# HDMI.net
KiCad netlist of a schematic drawn in Altium Designer
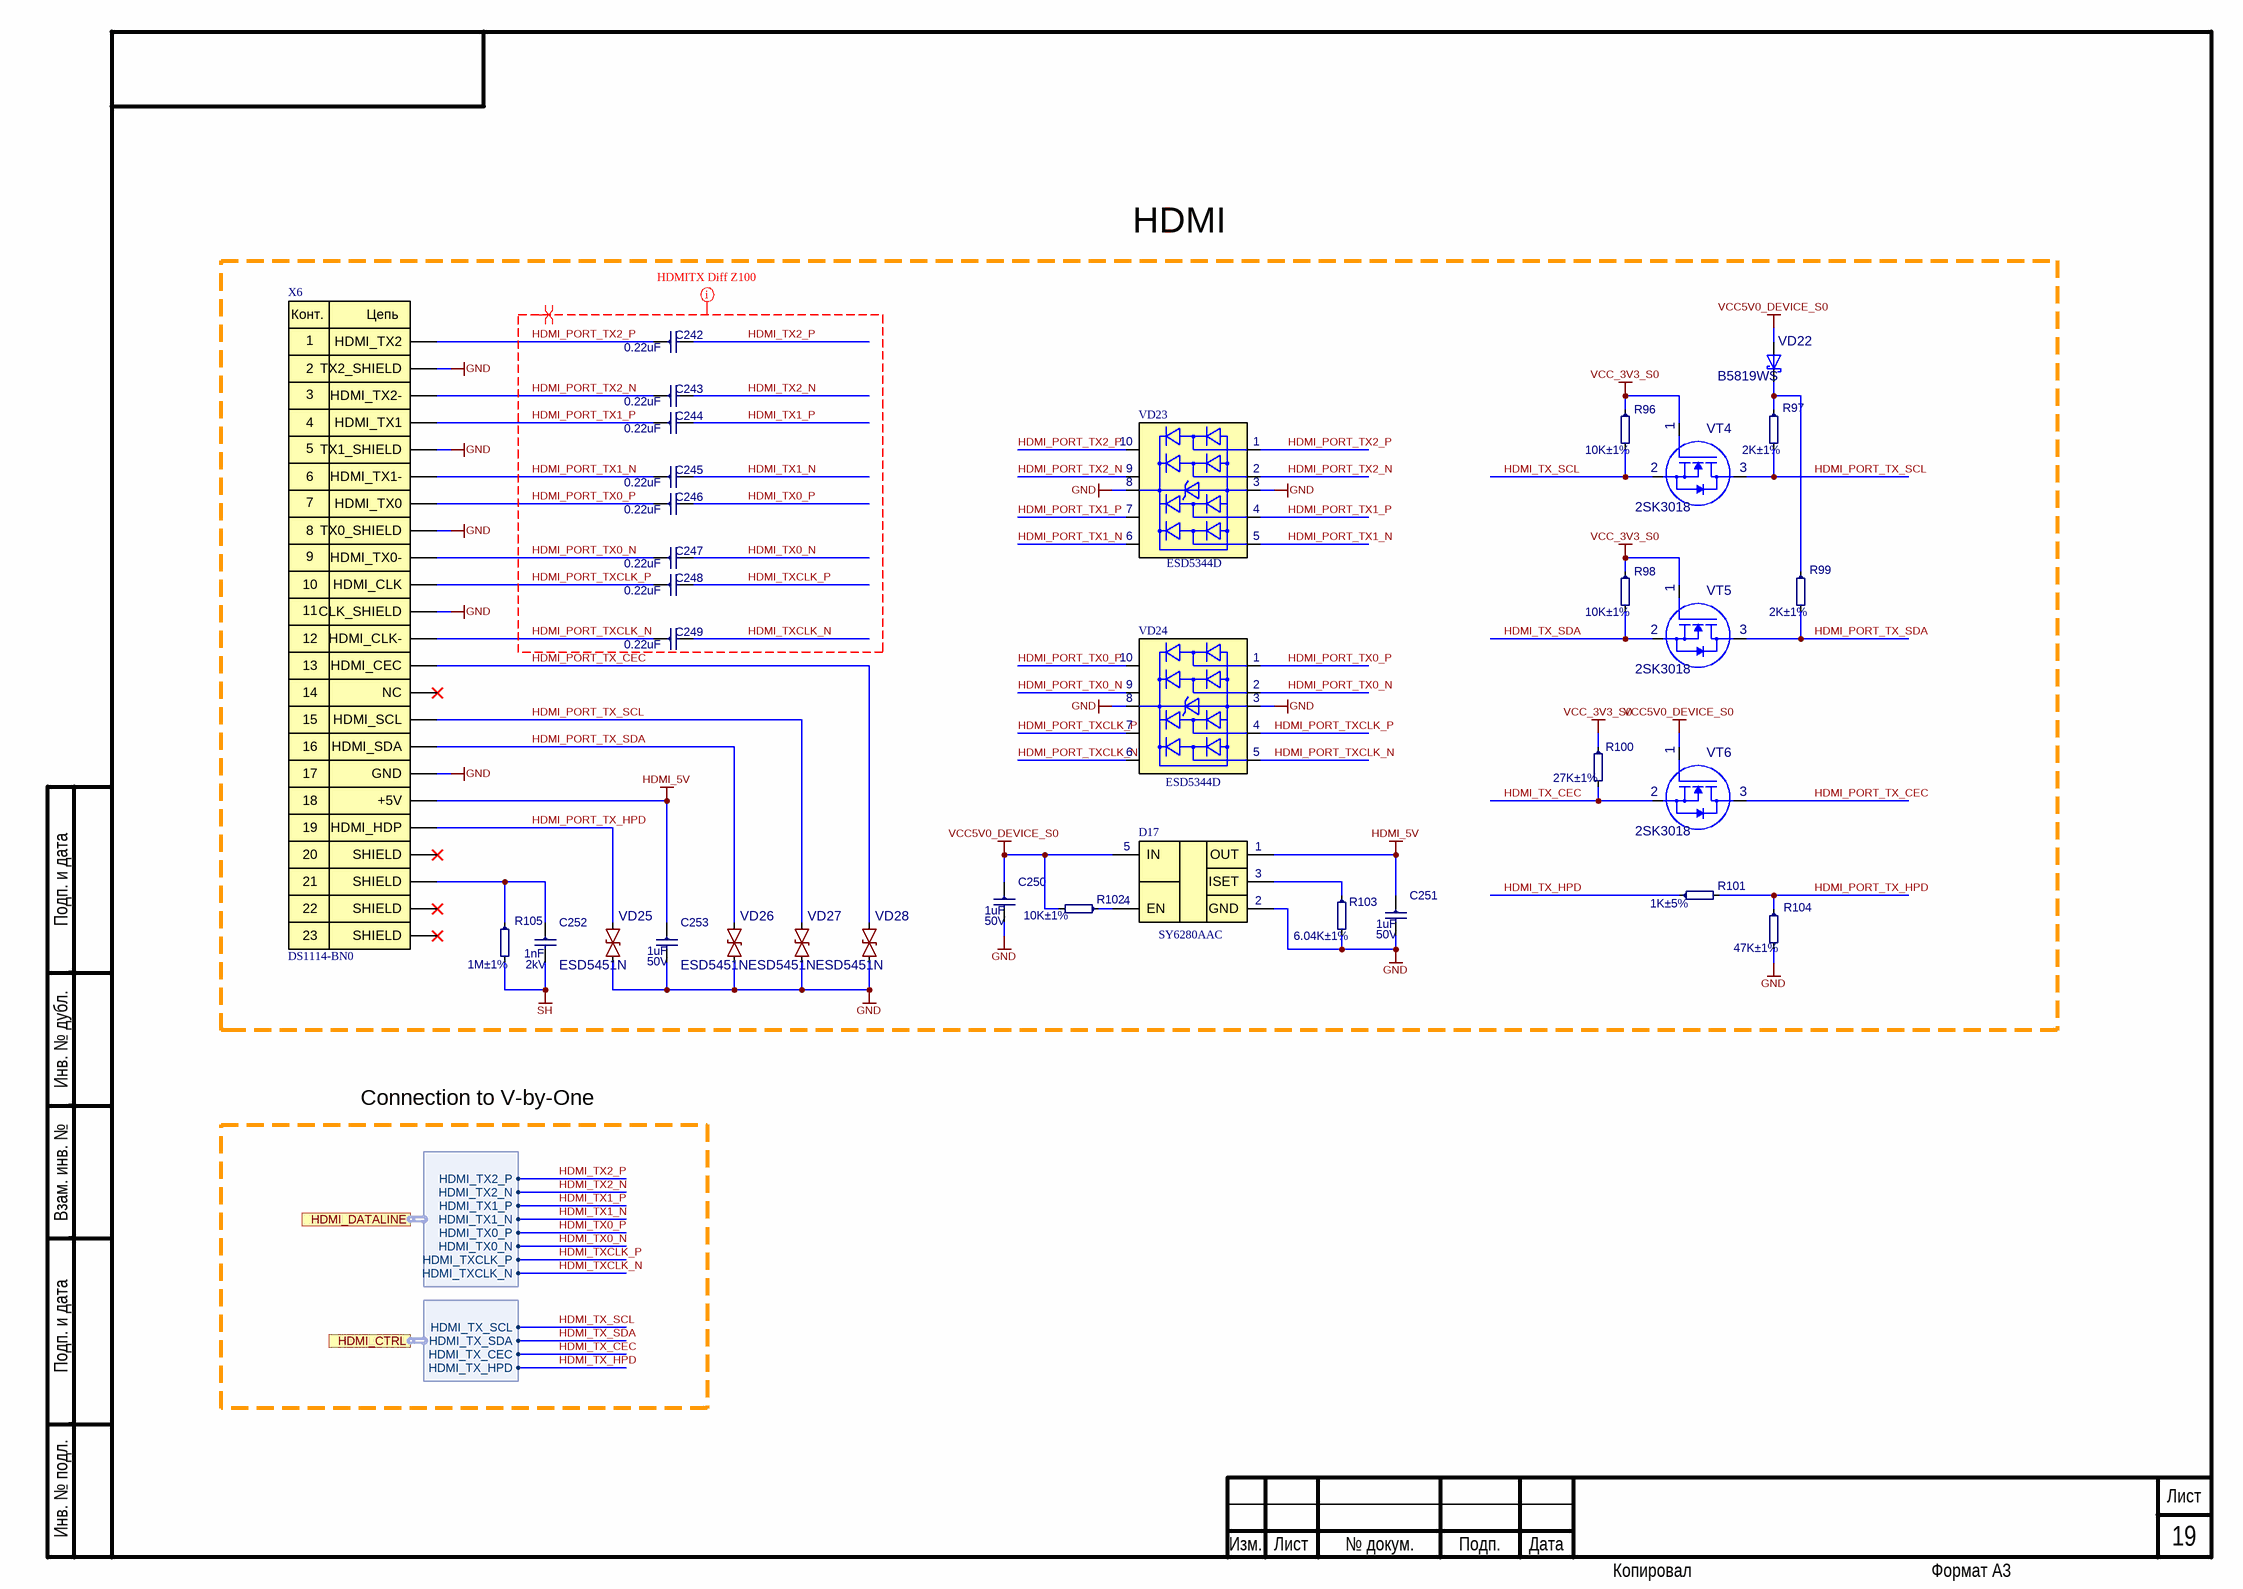
[diagram p0: HDMI.SchDoc]

(export (version "E")
  (design (tool "Eeschema 10.0.6"))
  (components
    (comp (ref "C242")
      (value "0.22uF")
      (footprint "C0201")
      (fields
        (field (name "VOLTAGE") "10V")
        (field (name "PART NUMBER") "0201-X5R-10V-220nF±10%")
        (field (name "TOLERANCE") "5%")
      )
      (libsource (lib "ATB") (part "C"))
    )
    (comp (ref "C243")
      (value "0.22uF")
      (footprint "C0201")
      (fields
        (field (name "VOLTAGE") "10V")
        (field (name "PART NUMBER") "0201-X5R-10V-220nF±10%")
        (field (name "TOLERANCE") "5%")
      )
      (libsource (lib "ATB") (part "C"))
    )
    (comp (ref "C244")
      (value "0.22uF")
      (footprint "C0201")
      (fields
        (field (name "VOLTAGE") "10V")
        (field (name "PART NUMBER") "0201-X5R-10V-220nF±10%")
        (field (name "TOLERANCE") "5%")
      )
      (libsource (lib "ATB") (part "C"))
    )
    (comp (ref "C245")
      (value "0.22uF")
      (footprint "C0201")
      (fields
        (field (name "VOLTAGE") "10V")
        (field (name "PART NUMBER") "0201-X5R-10V-220nF±10%")
        (field (name "TOLERANCE") "5%")
      )
      (libsource (lib "ATB") (part "C"))
    )
    (comp (ref "C246")
      (value "0.22uF")
      (footprint "C0201")
      (fields
        (field (name "VOLTAGE") "10V")
        (field (name "PART NUMBER") "0201-X5R-10V-220nF±10%")
        (field (name "TOLERANCE") "5%")
      )
      (libsource (lib "ATB") (part "C"))
    )
    (comp (ref "C247")
      (value "0.22uF")
      (footprint "C0201")
      (fields
        (field (name "VOLTAGE") "10V")
        (field (name "PART NUMBER") "0201-X5R-10V-220nF±10%")
        (field (name "TOLERANCE") "5%")
      )
      (libsource (lib "ATB") (part "C"))
    )
    (comp (ref "C248")
      (value "0.22uF")
      (footprint "C0201")
      (fields
        (field (name "VOLTAGE") "10V")
        (field (name "PART NUMBER") "0201-X5R-10V-220nF±10%")
        (field (name "TOLERANCE") "5%")
      )
      (libsource (lib "ATB") (part "C"))
    )
    (comp (ref "C249")
      (value "0.22uF")
      (footprint "C0201")
      (fields
        (field (name "VOLTAGE") "10V")
        (field (name "PART NUMBER") "0201-X5R-10V-220nF±10%")
        (field (name "TOLERANCE") "5%")
      )
      (libsource (lib "ATB") (part "C"))
    )
    (comp (ref "C250")
      (value "1uF")
      (footprint "C0402")
      (description "Ceramic Capacitor 0402 1uF ±10% 50V X5R")
      (fields
        (field (name "VOLTAGE") "50V")
        (field (name "PART NUMBER") "0402-X5R-50V-1uF±10%")
        (field (name "TOLERANCE") "10%")
      )
      (libsource (lib "ATB") (part "C"))
    )
    (comp (ref "C251")
      (value "1uF")
      (footprint "C0402")
      (description "Ceramic Capacitor 0402 1uF ±10% 50V X5R")
      (fields
        (field (name "VOLTAGE") "50V")
        (field (name "PART NUMBER") "0402-X5R-50V-1uF±10%")
        (field (name "TOLERANCE") "10%")
      )
      (libsource (lib "ATB") (part "C"))
    )
    (comp (ref "C252")
      (value "1nF")
      (footprint "C1812")
      (fields
        (field (name "VOLTAGE") "2kV")
        (field (name "PART NUMBER") "1812-C0G-2kV-1nF±10%")
        (field (name "TOLERANCE") "5%")
        (field (name "MANUFACTURER") "FH")
      )
      (libsource (lib "ATB") (part "C"))
    )
    (comp (ref "C253")
      (value "1uF")
      (footprint "C0402")
      (description "Ceramic Capacitor 0402 1uF ±10% 50V X5R")
      (fields
        (field (name "VOLTAGE") "50V")
        (field (name "PART NUMBER") "0402-X5R-50V-1uF±10%")
        (field (name "TOLERANCE") "10%")
      )
      (libsource (lib "ATB") (part "C"))
    )
    (comp (ref "D17")
      (value "SY6280AAC")
      (footprint "SY6280AAC")
      (description "Power Distribution Switches")
      (fields (field (name "MANUFACTURER") "Silergy Corp"))
      (libsource (lib "LIB_RK") (part "SY6280AAC"))
    )
    (comp (ref "R96")
      (value "10K±1%")
      (footprint "R0402")
      (description "Chip Resistor 0402 10kΩ ±1% 50V ±100ppm/℃ Thick Film")
      (fields (field (name "PART NUMBER") "0402-0.0625W-10K-100ppm±1%") (field (name "TOLERANCE") "1%"))
      (libsource (lib "ATB") (part "R"))
    )
    (comp (ref "R97")
      (value "2K±1%")
      (footprint "R0402")
      (fields
        (field (name "PART NUMBER") "0402-0.0625W-2K-100ppm±1%")
        (field (name "TOLERANCE") "1%")
        (field (name "MANUFACTURER") "Yageo")
      )
      (libsource (lib "ATB") (part "R"))
    )
    (comp (ref "R98")
      (value "10K±1%")
      (footprint "R0402")
      (description "Chip Resistor 0402 10kΩ ±1% 50V ±100ppm/℃ Thick Film")
      (fields (field (name "PART NUMBER") "0402-0.0625W-10K-100ppm±1%") (field (name "TOLERANCE") "1%"))
      (libsource (lib "ATB") (part "R"))
    )
    (comp (ref "R99")
      (value "2K±1%")
      (footprint "R0402")
      (fields
        (field (name "PART NUMBER") "0402-0.0625W-2K-100ppm±1%")
        (field (name "TOLERANCE") "1%")
        (field (name "MANUFACTURER") "Yageo")
      )
      (libsource (lib "ATB") (part "R"))
    )
    (comp (ref "R100")
      (value "27K±1%")
      (footprint "R0402")
      (fields
        (field (name "PART NUMBER") "0402-0.0625W-27K-100ppm±1%")
        (field (name "TOLERANCE") "1%")
        (field (name "MANUFACTURER") "Yageo")
      )
      (libsource (lib "ATB") (part "R"))
    )
    (comp (ref "R101")
      (value "1K±5%")
      (footprint "R0402")
      (fields
        (field (name "PART NUMBER") "0402-0.0625W-1K-100ppm±5%")
        (field (name "TOLERANCE") "5%")
        (field (name "MANUFACTURER") "Yageo")
      )
      (libsource (lib "ATB") (part "R"))
    )
    (comp (ref "R102")
      (value "10K±1%")
      (footprint "R0402")
      (description "Chip Resistor 0402 10kΩ ±1% 50V ±100ppm/℃ Thick Film")
      (fields (field (name "PART NUMBER") "0402-0.0625W-10K-100ppm±1%") (field (name "TOLERANCE") "1%"))
      (libsource (lib "ATB") (part "R"))
    )
    (comp (ref "R103")
      (value "6.04K±1%")
      (footprint "R0402")
      (fields
        (field (name "PART NUMBER") "0402-0.0625W-6.04K-100ppm±1%")
        (field (name "TOLERANCE") "1%")
        (field (name "MANUFACTURER") "Yageo")
      )
      (libsource (lib "ATB") (part "R"))
    )
    (comp (ref "R104")
      (value "47K±1%")
      (footprint "R0402")
      (fields
        (field (name "PART NUMBER") "0402-0.0625W-47K-100ppm±1%")
        (field (name "TOLERANCE") "1%")
        (field (name "MANUFACTURER") "Yageo")
      )
      (libsource (lib "ATB") (part "R"))
    )
    (comp (ref "R105")
      (value "1M±1%")
      (footprint "R1206")
      (description "Chip Resistor 1206 1MΩ ±1% 200V ±100ppm/℃ Thick Film")
      (fields (field (name "PART NUMBER") "1206-0.25W-1M-100ppm±1%") (field (name "TOLERANCE") "1%"))
      (libsource (lib "ATB") (part "R"))
    )
    (comp (ref "VD22")
      (value "B5819WS")
      (footprint "B5819WS")
      (fields (field (name "MANUFACTURER") "MDD"))
      (libsource (lib "LIB_RK") (part "B5819WS"))
    )
    (comp (ref "VD23")
      (value "ESD5344D")
      (footprint "ESD5344D")
      (fields (field (name "MANUFACTURER") "KUU"))
      (libsource (lib "LIB_RK") (part "ESD5344D"))
    )
    (comp (ref "VD24")
      (value "ESD5344D")
      (footprint "ESD5344D")
      (fields (field (name "MANUFACTURER") "KUU"))
      (libsource (lib "LIB_RK") (part "ESD5344D"))
    )
    (comp (ref "VD25")
      (value "ESD5451N")
      (footprint "DFN_1006_2")
      (description "Bidirectional TVS Diode 5V")
      (fields (field (name "MANUFACTURER") "Tech Public Co."))
      (libsource (lib "ATB") (part "ESD-BiDirectional"))
    )
    (comp (ref "VD26")
      (value "ESD5451N")
      (footprint "DFN_1006_2")
      (description "Bidirectional TVS Diode 5V")
      (fields (field (name "MANUFACTURER") "Tech Public Co."))
      (libsource (lib "ATB") (part "ESD-BiDirectional"))
    )
    (comp (ref "VD27")
      (value "ESD5451N")
      (footprint "DFN_1006_2")
      (description "Bidirectional TVS Diode 5V")
      (fields (field (name "MANUFACTURER") "Tech Public Co."))
      (libsource (lib "ATB") (part "ESD-BiDirectional"))
    )
    (comp (ref "VD28")
      (value "ESD5451N")
      (footprint "DFN_1006_2")
      (description "Bidirectional TVS Diode 5V")
      (fields (field (name "MANUFACTURER") "Tech Public Co."))
      (libsource (lib "ATB") (part "ESD-BiDirectional"))
    )
    (comp (ref "VT4")
      (value "2SK3018")
      (footprint "2SK3018")
      (description "N-Channel")
      (fields (field (name "MANUFACTURER") "KUU"))
      (libsource (lib "LIB_RK") (part "2SK3018"))
    )
    (comp (ref "VT5")
      (value "2SK3018")
      (footprint "2SK3018")
      (description "N-Channel")
      (fields (field (name "MANUFACTURER") "KUU"))
      (libsource (lib "LIB_RK") (part "2SK3018"))
    )
    (comp (ref "VT6")
      (value "2SK3018")
      (footprint "2SK3018")
      (description "N-Channel")
      (fields (field (name "MANUFACTURER") "KUU"))
      (libsource (lib "LIB_RK") (part "2SK3018"))
    )
    (comp (ref "X6")
      (value "DS1114-BN0")
      (footprint "DS1114-BN0")
      (fields (field (name "MANUFACTURER") "CONNFLY"))
      (libsource (lib "LIB_RK") (part "DS1114-BN0"))
    )
  )
  (nets
    (net (code "3") (name "/HDMI_PORT_TX0_N") (class "Default")
      (node (ref "C247") (pin "1") (pinfunction "1_1") (pintype "passive"))
      (node (ref "VD24") (pin "2") (pinfunction "2_2") (pintype "passive"))
      (node (ref "VD24") (pin "9") (pinfunction "9_9") (pintype "passive"))
      (node (ref "X6") (pin "9") (pinfunction "HDMI_TX0-_9") (pintype "passive"))
    )
    (net (code "4") (name "/HDMI_PORT_TX0_P") (class "Default")
      (node (ref "C246") (pin "1") (pinfunction "1_1") (pintype "passive"))
      (node (ref "VD24") (pin "1") (pinfunction "1_1") (pintype "passive"))
      (node (ref "VD24") (pin "10") (pinfunction "10_10") (pintype "passive"))
      (node (ref "X6") (pin "7") (pinfunction "HDMI_TX0_7") (pintype "passive"))
    )
    (net (code "5") (name "/HDMI_PORT_TX1_N") (class "Default")
      (node (ref "C245") (pin "1") (pinfunction "1_1") (pintype "passive"))
      (node (ref "VD23") (pin "5") (pinfunction "5_5") (pintype "passive"))
      (node (ref "VD23") (pin "6") (pinfunction "6_6") (pintype "passive"))
      (node (ref "X6") (pin "6") (pinfunction "HDMI_TX1-_6") (pintype "passive"))
    )
    (net (code "6") (name "/HDMI_PORT_TX1_P") (class "Default")
      (node (ref "C244") (pin "1") (pinfunction "1_1") (pintype "passive"))
      (node (ref "VD23") (pin "4") (pinfunction "4_4") (pintype "passive"))
      (node (ref "VD23") (pin "7") (pinfunction "7_7") (pintype "passive"))
      (node (ref "X6") (pin "4") (pinfunction "HDMI_TX1_4") (pintype "passive"))
    )
    (net (code "7") (name "/HDMI_PORT_TX2_N") (class "Default")
      (node (ref "C243") (pin "1") (pinfunction "1_1") (pintype "passive"))
      (node (ref "VD23") (pin "2") (pinfunction "2_2") (pintype "passive"))
      (node (ref "VD23") (pin "9") (pinfunction "9_9") (pintype "passive"))
      (node (ref "X6") (pin "3") (pinfunction "HDMI_TX2-_3") (pintype "passive"))
    )
    (net (code "8") (name "/HDMI_PORT_TX2_P") (class "Default")
      (node (ref "C242") (pin "1") (pinfunction "1_1") (pintype "passive"))
      (node (ref "VD23") (pin "1") (pinfunction "1_1") (pintype "passive"))
      (node (ref "VD23") (pin "10") (pinfunction "10_10") (pintype "passive"))
      (node (ref "X6") (pin "1") (pinfunction "HDMI_TX2_1") (pintype "passive"))
    )
    (net (code "9") (name "/HDMI_PORT_TXCLK_N") (class "Default")
      (node (ref "C249") (pin "1") (pinfunction "1_1") (pintype "passive"))
      (node (ref "VD24") (pin "5") (pinfunction "5_5") (pintype "passive"))
      (node (ref "VD24") (pin "6") (pinfunction "6_6") (pintype "passive"))
      (node (ref "X6") (pin "12") (pinfunction "HDMI_CLK-_12") (pintype "passive"))
    )
    (net (code "10") (name "/HDMI_PORT_TXCLK_P") (class "Default")
      (node (ref "C248") (pin "1") (pinfunction "1_1") (pintype "passive"))
      (node (ref "VD24") (pin "4") (pinfunction "4_4") (pintype "passive"))
      (node (ref "VD24") (pin "7") (pinfunction "7_7") (pintype "passive"))
      (node (ref "X6") (pin "10") (pinfunction "HDMI_CLK_10") (pintype "passive"))
    )
    (net (code "11") (name "/HDMI_PORT_TX_CEC") (class "Default")
      (node (ref "VD28") (pin "1") (pinfunction "1_1") (pintype "passive"))
      (node (ref "VT6") (pin "3") (pinfunction "D_3") (pintype "passive"))
      (node (ref "X6") (pin "13") (pinfunction "HDMI_CEC_13") (pintype "passive"))
    )
    (net (code "12") (name "/HDMI_PORT_TX_HPD") (class "Default")
      (node (ref "R101") (pin "2") (pinfunction "2_2") (pintype "passive"))
      (node (ref "R104") (pin "1") (pinfunction "1_1") (pintype "passive"))
      (node (ref "VD25") (pin "1") (pinfunction "1_1") (pintype "passive"))
      (node (ref "X6") (pin "19") (pinfunction "HDMI_HDP_19") (pintype "passive"))
    )
    (net (code "13") (name "/HDMI_PORT_TX_SCL") (class "Default")
      (node (ref "R97") (pin "2") (pinfunction "2_2") (pintype "passive"))
      (node (ref "VD27") (pin "1") (pinfunction "1_1") (pintype "passive"))
      (node (ref "VT4") (pin "3") (pinfunction "D_3") (pintype "passive"))
      (node (ref "X6") (pin "15") (pinfunction "HDMI_SCL_15") (pintype "passive"))
    )
    (net (code "14") (name "/HDMI_PORT_TX_SDA") (class "Default")
      (node (ref "R99") (pin "2") (pinfunction "2_2") (pintype "passive"))
      (node (ref "VD26") (pin "1") (pinfunction "1_1") (pintype "passive"))
      (node (ref "VT5") (pin "3") (pinfunction "D_3") (pintype "passive"))
      (node (ref "X6") (pin "16") (pinfunction "HDMI_SDA_16") (pintype "passive"))
    )
    (net (code "15") (name "/HDMI_TX0_N") (class "Default")
      (node (ref "C247") (pin "2") (pinfunction "2_2") (pintype "passive"))
    )
    (net (code "16") (name "/HDMI_TX0_P") (class "Default")
      (node (ref "C246") (pin "2") (pinfunction "2_2") (pintype "passive"))
    )
    (net (code "17") (name "/HDMI_TX1_N") (class "Default")
      (node (ref "C245") (pin "2") (pinfunction "2_2") (pintype "passive"))
    )
    (net (code "18") (name "/HDMI_TX1_P") (class "Default")
      (node (ref "C244") (pin "2") (pinfunction "2_2") (pintype "passive"))
    )
    (net (code "19") (name "/HDMI_TX2_N") (class "Default")
      (node (ref "C243") (pin "2") (pinfunction "2_2") (pintype "passive"))
    )
    (net (code "20") (name "/HDMI_TX2_P") (class "Default")
      (node (ref "C242") (pin "2") (pinfunction "2_2") (pintype "passive"))
    )
    (net (code "21") (name "/HDMI_TXCLK_N") (class "Default")
      (node (ref "C249") (pin "2") (pinfunction "2_2") (pintype "passive"))
    )
    (net (code "22") (name "/HDMI_TXCLK_P") (class "Default")
      (node (ref "C248") (pin "2") (pinfunction "2_2") (pintype "passive"))
    )
    (net (code "23") (name "/HDMI_TX_CEC") (class "Default")
      (node (ref "R100") (pin "2") (pinfunction "2_2") (pintype "passive"))
      (node (ref "VT6") (pin "2") (pinfunction "S_2") (pintype "passive"))
    )
    (net (code "24") (name "/HDMI_TX_HPD") (class "Default")
      (node (ref "R101") (pin "1") (pinfunction "1_1") (pintype "passive"))
    )
    (net (code "25") (name "/HDMI_TX_SCL") (class "Default")
      (node (ref "R96") (pin "2") (pinfunction "2_2") (pintype "passive"))
      (node (ref "VT4") (pin "2") (pinfunction "S_2") (pintype "passive"))
    )
    (net (code "26") (name "/HDMI_TX_SDA") (class "Default")
      (node (ref "R98") (pin "2") (pinfunction "2_2") (pintype "passive"))
      (node (ref "VT5") (pin "2") (pinfunction "S_2") (pintype "passive"))
    )
    (net (code "29") (name "GND") (class "Default")
      (node (ref "C250") (pin "2") (pinfunction "2_2") (pintype "passive"))
      (node (ref "C251") (pin "2") (pinfunction "2_2") (pintype "passive"))
      (node (ref "C253") (pin "2") (pinfunction "2_2") (pintype "passive"))
      (node (ref "D17") (pin "2") (pinfunction "GND_2") (pintype "passive"))
      (node (ref "R103") (pin "2") (pinfunction "2_2") (pintype "passive"))
      (node (ref "R104") (pin "2") (pinfunction "2_2") (pintype "passive"))
      (node (ref "VD23") (pin "3") (pinfunction "3_3") (pintype "passive"))
      (node (ref "VD23") (pin "8") (pinfunction "8_8") (pintype "passive"))
      (node (ref "VD24") (pin "3") (pinfunction "3_3") (pintype "passive"))
      (node (ref "VD24") (pin "8") (pinfunction "8_8") (pintype "passive"))
      (node (ref "VD25") (pin "2") (pinfunction "2_2") (pintype "passive"))
      (node (ref "VD26") (pin "2") (pinfunction "2_2") (pintype "passive"))
      (node (ref "VD27") (pin "2") (pinfunction "2_2") (pintype "passive"))
      (node (ref "VD28") (pin "2") (pinfunction "2_2") (pintype "passive"))
      (node (ref "X6") (pin "11") (pinfunction "CLK_SHIELD_11") (pintype "passive"))
      (node (ref "X6") (pin "17") (pinfunction "GND_17") (pintype "passive"))
      (node (ref "X6") (pin "2") (pinfunction "TX2_SHIELD_2") (pintype "passive"))
      (node (ref "X6") (pin "5") (pinfunction "TX1_SHIELD_5") (pintype "passive"))
      (node (ref "X6") (pin "8") (pinfunction "TX0_SHIELD_8") (pintype "passive"))
    )
    (net (code "30") (name "HDMI_5V") (class "Default")
      (node (ref "C251") (pin "1") (pinfunction "1_1") (pintype "passive"))
      (node (ref "C253") (pin "1") (pinfunction "1_1") (pintype "passive"))
      (node (ref "D17") (pin "1") (pinfunction "OUT_1") (pintype "passive"))
      (node (ref "X6") (pin "18") (pinfunction "+5V_18") (pintype "passive"))
    )
    (net (code "31") (name "Net-(C252-Pad1)") (class "Default")
      (node (ref "C252") (pin "1") (pinfunction "1_1") (pintype "passive"))
      (node (ref "R105") (pin "1") (pinfunction "1_1") (pintype "passive"))
      (node (ref "X6") (pin "21") (pinfunction "SHIELD_21") (pintype "passive"))
    )
    (net (code "32") (name "Net-(D17-EN)") (class "Default")
      (node (ref "D17") (pin "4") (pinfunction "EN_4") (pintype "passive"))
      (node (ref "R102") (pin "1") (pinfunction "1_1") (pintype "passive"))
    )
    (net (code "33") (name "Net-(D17-ISET)") (class "Default")
      (node (ref "D17") (pin "3") (pinfunction "ISET_3") (pintype "passive"))
      (node (ref "R103") (pin "1") (pinfunction "1_1") (pintype "passive"))
    )
    (net (code "34") (name "Net-(VD22-K)") (class "Default")
      (node (ref "R97") (pin "1") (pinfunction "1_1") (pintype "passive"))
      (node (ref "R99") (pin "1") (pinfunction "1_1") (pintype "passive"))
      (node (ref "VD22") (pin "1") (pinfunction "K_1") (pintype "passive"))
    )
    (net (code "35") (name "SH") (class "Default")
      (node (ref "C252") (pin "2") (pinfunction "2_2") (pintype "passive"))
      (node (ref "R105") (pin "2") (pinfunction "2_2") (pintype "passive"))
    )
    (net (code "36") (name "VCC5V0_DEVICE_S0") (class "Default")
      (node (ref "C250") (pin "1") (pinfunction "1_1") (pintype "passive"))
      (node (ref "D17") (pin "5") (pinfunction "IN_5") (pintype "passive"))
      (node (ref "R102") (pin "2") (pinfunction "2_2") (pintype "passive"))
      (node (ref "VD22") (pin "2") (pinfunction "A_2") (pintype "passive"))
      (node (ref "VT6") (pin "1") (pinfunction "G_1") (pintype "passive"))
    )
    (net (code "37") (name "VCC_3V3_S0") (class "Default")
      (node (ref "R100") (pin "1") (pinfunction "1_1") (pintype "passive"))
      (node (ref "R96") (pin "1") (pinfunction "1_1") (pintype "passive"))
      (node (ref "R98") (pin "1") (pinfunction "1_1") (pintype "passive"))
      (node (ref "VT4") (pin "1") (pinfunction "G_1") (pintype "passive"))
      (node (ref "VT5") (pin "1") (pinfunction "G_1") (pintype "passive"))
    )
    (net (code "38") (name "unconnected-(X6-NC-Pad14)") (class "Default")
      (node (ref "X6") (pin "14") (pinfunction "NC_14") (pintype "passive+no_connect"))
    )
    (net (code "39") (name "unconnected-(X6-SHIELD-Pad20)") (class "Default")
      (node (ref "X6") (pin "20") (pinfunction "SHIELD_20") (pintype "passive+no_connect"))
    )
    (net (code "40") (name "unconnected-(X6-SHIELD-Pad22)") (class "Default")
      (node (ref "X6") (pin "22") (pinfunction "SHIELD_22") (pintype "passive+no_connect"))
    )
    (net (code "41") (name "unconnected-(X6-SHIELD-Pad23)") (class "Default")
      (node (ref "X6") (pin "23") (pinfunction "SHIELD_23") (pintype "passive+no_connect"))
    )
  )
)
